# balance.net
KiCad netlist of a schematic drawn in EAGLE
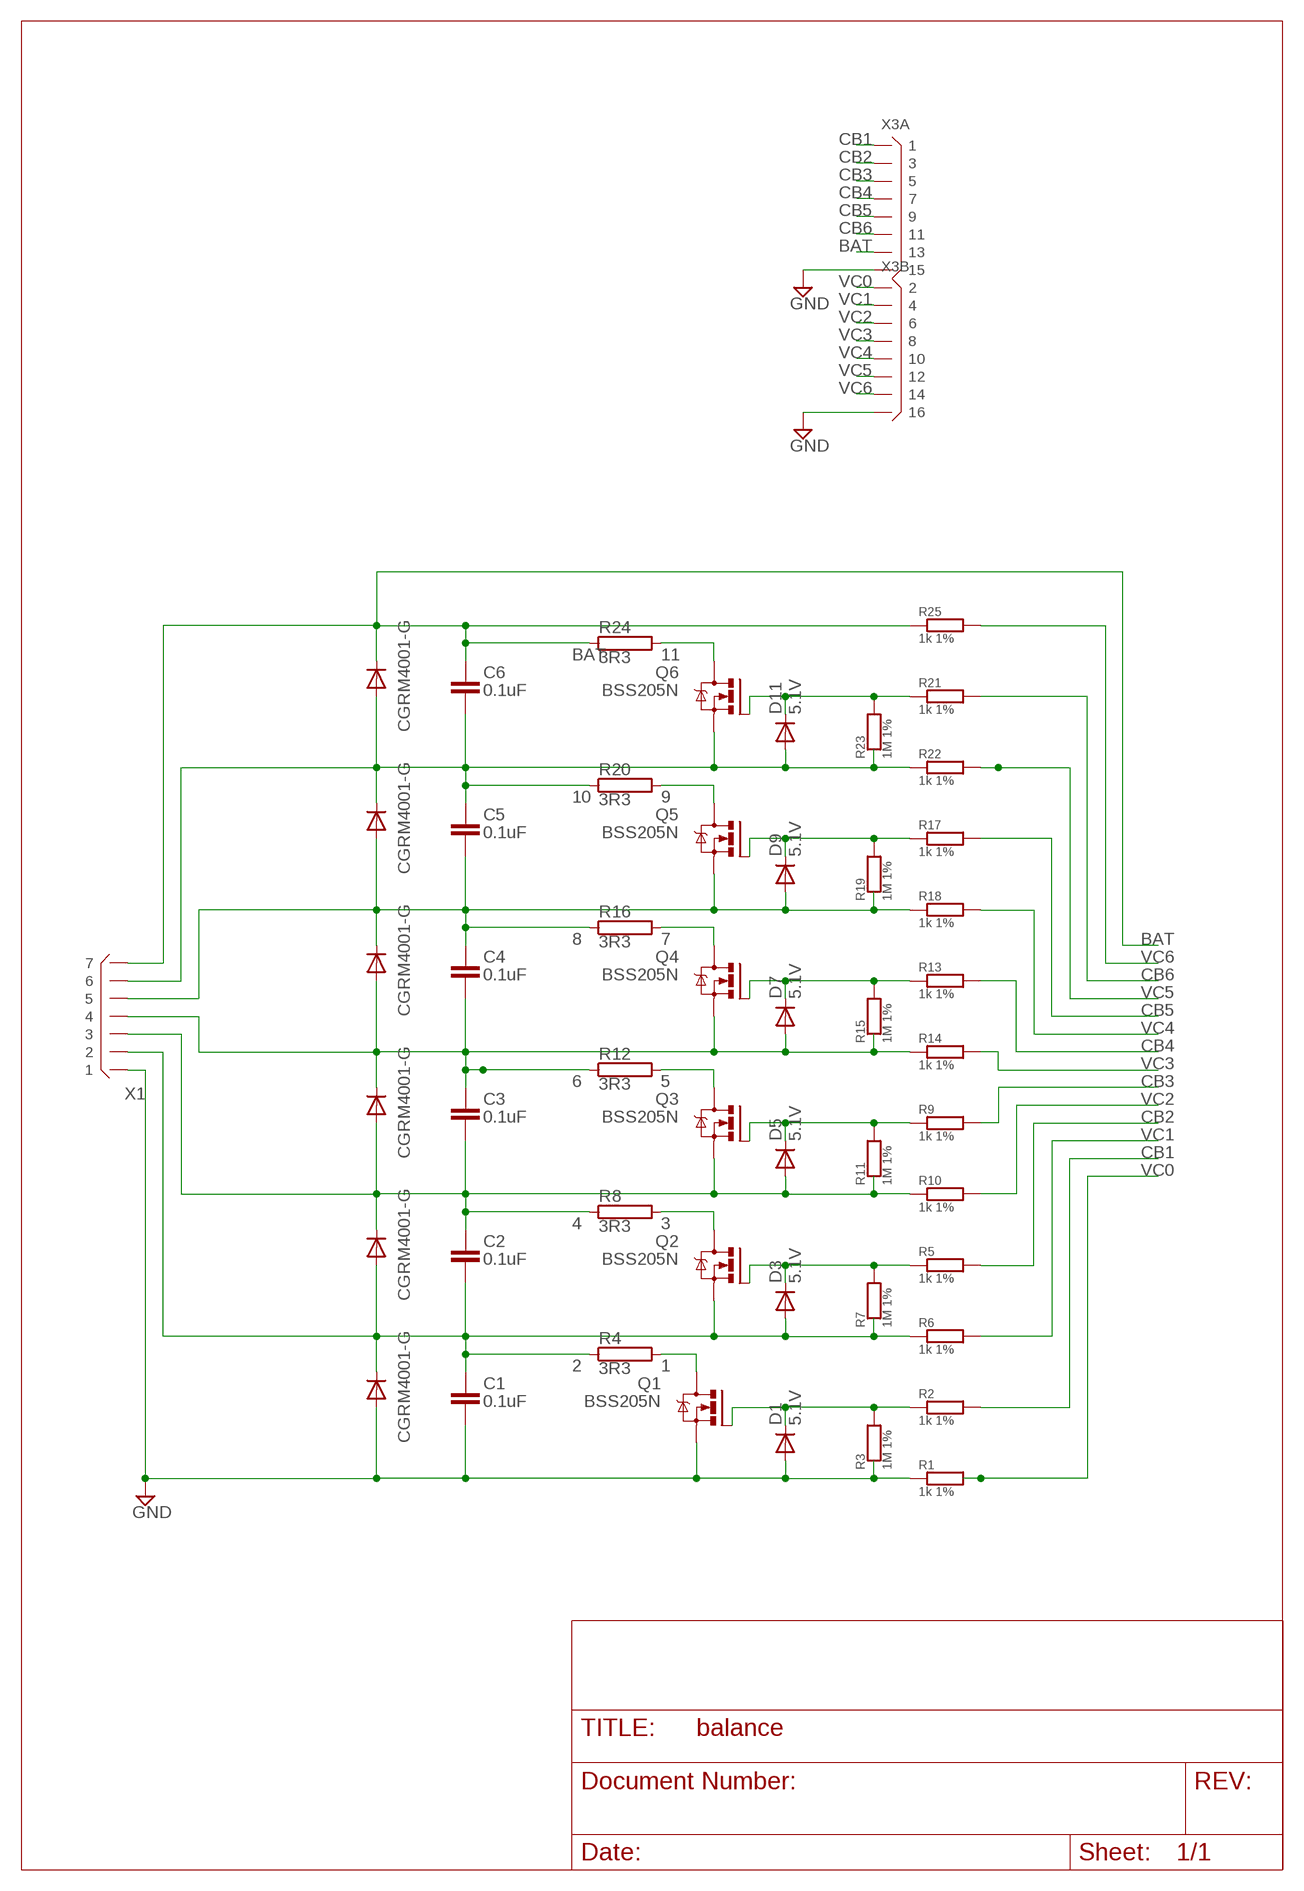
[diagram p0: schematic, sheet 1]

(export (version "E")
  (design (tool "Eeschema 10.0.6"))
  (components
    (comp (ref "C1")
      (value "0.1uF")
      (footprint "eagle-import:C0805")
      (libsource (lib "eagle-import") (part "CSTD"))
    )
    (comp (ref "C2")
      (value "0.1uF")
      (footprint "eagle-import:C0805")
      (libsource (lib "eagle-import") (part "CSTD"))
    )
    (comp (ref "C3")
      (value "0.1uF")
      (footprint "eagle-import:C0805")
      (libsource (lib "eagle-import") (part "CSTD"))
    )
    (comp (ref "C4")
      (value "0.1uF")
      (footprint "eagle-import:C0805")
      (libsource (lib "eagle-import") (part "CSTD"))
    )
    (comp (ref "C5")
      (value "0.1uF")
      (footprint "eagle-import:C0805")
      (libsource (lib "eagle-import") (part "CSTD"))
    )
    (comp (ref "C6")
      (value "0.1uF")
      (footprint "eagle-import:C0805")
      (libsource (lib "eagle-import") (part "CSTD"))
    )
    (comp (ref "D1")
      (value "5.1V")
      (footprint "eagle-import:SOD-323")
      (libsource (lib "eagle-import") (part "DIODESOD"))
    )
    (comp (ref "D2")
      (value "CGRM4001-G")
      (footprint "eagle-import:SOD-123_MINI-SMA")
      (libsource (lib "eagle-import") (part "CGRM400-G1"))
    )
    (comp (ref "D3")
      (value "5.1V")
      (footprint "eagle-import:SOD-323")
      (libsource (lib "eagle-import") (part "DIODESOD"))
    )
    (comp (ref "D4")
      (value "CGRM4001-G")
      (footprint "eagle-import:SOD-123_MINI-SMA")
      (libsource (lib "eagle-import") (part "CGRM400-G1"))
    )
    (comp (ref "D5")
      (value "5.1V")
      (footprint "eagle-import:SOD-323")
      (libsource (lib "eagle-import") (part "DIODESOD"))
    )
    (comp (ref "D6")
      (value "CGRM4001-G")
      (footprint "eagle-import:SOD-123_MINI-SMA")
      (libsource (lib "eagle-import") (part "CGRM400-G1"))
    )
    (comp (ref "D7")
      (value "5.1V")
      (footprint "eagle-import:SOD-323")
      (libsource (lib "eagle-import") (part "DIODESOD"))
    )
    (comp (ref "D8")
      (value "CGRM4001-G")
      (footprint "eagle-import:SOD-123_MINI-SMA")
      (libsource (lib "eagle-import") (part "CGRM400-G1"))
    )
    (comp (ref "D9")
      (value "5.1V")
      (footprint "eagle-import:SOD-323")
      (libsource (lib "eagle-import") (part "DIODESOD"))
    )
    (comp (ref "D10")
      (value "CGRM4001-G")
      (footprint "eagle-import:SOD-123_MINI-SMA")
      (libsource (lib "eagle-import") (part "CGRM400-G1"))
    )
    (comp (ref "D11")
      (value "5.1V")
      (footprint "eagle-import:SOD-323")
      (libsource (lib "eagle-import") (part "DIODESOD"))
    )
    (comp (ref "D12")
      (value "CGRM4001-G")
      (footprint "eagle-import:SOD-123_MINI-SMA")
      (libsource (lib "eagle-import") (part "CGRM400-G1"))
    )
    (comp (ref "Q1")
      (value "BSS205N")
      (footprint "eagle-import:SOT23")
      (libsource (lib "eagle-import") (part "BSS205N"))
    )
    (comp (ref "Q2")
      (value "BSS205N")
      (footprint "eagle-import:SOT23")
      (libsource (lib "eagle-import") (part "BSS205N"))
    )
    (comp (ref "Q3")
      (value "BSS205N")
      (footprint "eagle-import:SOT23")
      (libsource (lib "eagle-import") (part "BSS205N"))
    )
    (comp (ref "Q4")
      (value "BSS205N")
      (footprint "eagle-import:SOT23")
      (libsource (lib "eagle-import") (part "BSS205N"))
    )
    (comp (ref "Q5")
      (value "BSS205N")
      (footprint "eagle-import:SOT23")
      (libsource (lib "eagle-import") (part "BSS205N"))
    )
    (comp (ref "Q6")
      (value "BSS205N")
      (footprint "eagle-import:SOT23")
      (libsource (lib "eagle-import") (part "BSS205N"))
    )
    (comp (ref "R1")
      (value "1k 1%")
      (footprint "eagle-import:R0805")
      (libsource (lib "eagle-import") (part "useful_R"))
    )
    (comp (ref "R2")
      (value "1k 1%")
      (footprint "eagle-import:R0805")
      (libsource (lib "eagle-import") (part "useful_R"))
    )
    (comp (ref "R3")
      (value "1M 1%")
      (footprint "eagle-import:R0805")
      (libsource (lib "eagle-import") (part "useful_R"))
    )
    (comp (ref "R4")
      (value "3R3")
      (footprint "eagle-import:HS15")
      (libsource (lib "eagle-import") (part "R"))
    )
    (comp (ref "R5")
      (value "1k 1%")
      (footprint "eagle-import:R0805")
      (libsource (lib "eagle-import") (part "useful_R"))
    )
    (comp (ref "R6")
      (value "1k 1%")
      (footprint "eagle-import:R0805")
      (libsource (lib "eagle-import") (part "useful_R"))
    )
    (comp (ref "R7")
      (value "1M 1%")
      (footprint "eagle-import:R0805")
      (libsource (lib "eagle-import") (part "useful_R"))
    )
    (comp (ref "R8")
      (value "3R3")
      (footprint "eagle-import:HS15")
      (libsource (lib "eagle-import") (part "R"))
    )
    (comp (ref "R9")
      (value "1k 1%")
      (footprint "eagle-import:R0805")
      (libsource (lib "eagle-import") (part "useful_R"))
    )
    (comp (ref "R10")
      (value "1k 1%")
      (footprint "eagle-import:R0805")
      (libsource (lib "eagle-import") (part "useful_R"))
    )
    (comp (ref "R11")
      (value "1M 1%")
      (footprint "eagle-import:R0805")
      (libsource (lib "eagle-import") (part "useful_R"))
    )
    (comp (ref "R12")
      (value "3R3")
      (footprint "eagle-import:HS15")
      (libsource (lib "eagle-import") (part "R"))
    )
    (comp (ref "R13")
      (value "1k 1%")
      (footprint "eagle-import:R0805")
      (libsource (lib "eagle-import") (part "useful_R"))
    )
    (comp (ref "R14")
      (value "1k 1%")
      (footprint "eagle-import:R0805")
      (libsource (lib "eagle-import") (part "useful_R"))
    )
    (comp (ref "R15")
      (value "1M 1%")
      (footprint "eagle-import:R0805")
      (libsource (lib "eagle-import") (part "useful_R"))
    )
    (comp (ref "R16")
      (value "3R3")
      (footprint "eagle-import:HS15")
      (libsource (lib "eagle-import") (part "R"))
    )
    (comp (ref "R17")
      (value "1k 1%")
      (footprint "eagle-import:R0805")
      (libsource (lib "eagle-import") (part "useful_R"))
    )
    (comp (ref "R18")
      (value "1k 1%")
      (footprint "eagle-import:R0805")
      (libsource (lib "eagle-import") (part "useful_R"))
    )
    (comp (ref "R19")
      (value "1M 1%")
      (footprint "eagle-import:R0805")
      (libsource (lib "eagle-import") (part "useful_R"))
    )
    (comp (ref "R20")
      (value "3R3")
      (footprint "eagle-import:HS15")
      (libsource (lib "eagle-import") (part "R"))
    )
    (comp (ref "R21")
      (value "1k 1%")
      (footprint "eagle-import:R0805")
      (libsource (lib "eagle-import") (part "useful_R"))
    )
    (comp (ref "R22")
      (value "1k 1%")
      (footprint "eagle-import:R0805")
      (libsource (lib "eagle-import") (part "useful_R"))
    )
    (comp (ref "R23")
      (value "1M 1%")
      (footprint "eagle-import:R0805")
      (libsource (lib "eagle-import") (part "useful_R"))
    )
    (comp (ref "R24")
      (value "3R3")
      (footprint "eagle-import:HS15")
      (libsource (lib "eagle-import") (part "R"))
    )
    (comp (ref "R25")
      (value "1k 1%")
      (footprint "eagle-import:R0805")
      (libsource (lib "eagle-import") (part "useful_R"))
    )
    (comp (ref "X1")
      (value "B7B-XH")
      (footprint "eagle-import:B7B-XH")
      (libsource (lib "eagle-import") (part "?7B-XHB"))
    )
    (comp (ref "X3")
      (value "X08X2DR")
      (footprint "eagle-import:X16R-DIL")
      (libsource (lib "eagle-import") (part "X08X2DR"))
    )
  )
  (nets
    (net (code "1") (name "/1") (class "Default")
      (node (ref "Q1") (pin "3") (pinfunction "D_3") (pintype "passive"))
      (node (ref "R4") (pin "2") (pinfunction "2_2") (pintype "passive"))
    )
    (net (code "2") (name "/2") (class "Default")
      (node (ref "C1") (pin "2") (pinfunction "2_2") (pintype "passive"))
      (node (ref "C2") (pin "1") (pinfunction "1_1") (pintype "passive"))
      (node (ref "D2") (pin "C") (pinfunction "C_C") (pintype "passive"))
      (node (ref "D3") (pin "2") (pinfunction "A_2") (pintype "passive"))
      (node (ref "D4") (pin "A") (pinfunction "A_A") (pintype "passive"))
      (node (ref "Q2") (pin "2") (pinfunction "S_2") (pintype "passive"))
      (node (ref "R4") (pin "1") (pinfunction "1_1") (pintype "passive"))
      (node (ref "R6") (pin "1") (pinfunction "1_1") (pintype "passive"))
      (node (ref "R7") (pin "1") (pinfunction "1_1") (pintype "passive"))
      (node (ref "X1") (pin "P$2") (pinfunction "2_P$2") (pintype "bidirectional"))
    )
    (net (code "3") (name "/3") (class "Default")
      (node (ref "Q2") (pin "3") (pinfunction "D_3") (pintype "passive"))
      (node (ref "R8") (pin "2") (pinfunction "2_2") (pintype "passive"))
    )
    (net (code "4") (name "/4") (class "Default")
      (node (ref "C2") (pin "2") (pinfunction "2_2") (pintype "passive"))
      (node (ref "C3") (pin "1") (pinfunction "1_1") (pintype "passive"))
      (node (ref "D4") (pin "C") (pinfunction "C_C") (pintype "passive"))
      (node (ref "D5") (pin "2") (pinfunction "A_2") (pintype "passive"))
      (node (ref "D6") (pin "A") (pinfunction "A_A") (pintype "passive"))
      (node (ref "Q3") (pin "2") (pinfunction "S_2") (pintype "passive"))
      (node (ref "R10") (pin "1") (pinfunction "1_1") (pintype "passive"))
      (node (ref "R11") (pin "1") (pinfunction "1_1") (pintype "passive"))
      (node (ref "R8") (pin "1") (pinfunction "1_1") (pintype "passive"))
      (node (ref "X1") (pin "P$3") (pinfunction "3_P$3") (pintype "bidirectional"))
    )
    (net (code "5") (name "/5") (class "Default")
      (node (ref "Q3") (pin "3") (pinfunction "D_3") (pintype "passive"))
      (node (ref "R12") (pin "2") (pinfunction "2_2") (pintype "passive"))
    )
    (net (code "6") (name "/6") (class "Default")
      (node (ref "C3") (pin "2") (pinfunction "2_2") (pintype "passive"))
      (node (ref "C4") (pin "1") (pinfunction "1_1") (pintype "passive"))
      (node (ref "D6") (pin "C") (pinfunction "C_C") (pintype "passive"))
      (node (ref "D7") (pin "2") (pinfunction "A_2") (pintype "passive"))
      (node (ref "D8") (pin "A") (pinfunction "A_A") (pintype "passive"))
      (node (ref "Q4") (pin "2") (pinfunction "S_2") (pintype "passive"))
      (node (ref "R12") (pin "1") (pinfunction "1_1") (pintype "passive"))
      (node (ref "R14") (pin "1") (pinfunction "1_1") (pintype "passive"))
      (node (ref "R15") (pin "1") (pinfunction "1_1") (pintype "passive"))
      (node (ref "X1") (pin "P$4") (pinfunction "4_P$4") (pintype "bidirectional"))
    )
    (net (code "7") (name "/7") (class "Default")
      (node (ref "Q4") (pin "3") (pinfunction "D_3") (pintype "passive"))
      (node (ref "R16") (pin "2") (pinfunction "2_2") (pintype "passive"))
    )
    (net (code "8") (name "/8") (class "Default")
      (node (ref "C4") (pin "2") (pinfunction "2_2") (pintype "passive"))
      (node (ref "C5") (pin "1") (pinfunction "1_1") (pintype "passive"))
      (node (ref "D10") (pin "A") (pinfunction "A_A") (pintype "passive"))
      (node (ref "D8") (pin "C") (pinfunction "C_C") (pintype "passive"))
      (node (ref "D9") (pin "2") (pinfunction "A_2") (pintype "passive"))
      (node (ref "Q5") (pin "2") (pinfunction "S_2") (pintype "passive"))
      (node (ref "R16") (pin "1") (pinfunction "1_1") (pintype "passive"))
      (node (ref "R18") (pin "1") (pinfunction "1_1") (pintype "passive"))
      (node (ref "R19") (pin "1") (pinfunction "1_1") (pintype "passive"))
      (node (ref "X1") (pin "P$5") (pinfunction "5_P$5") (pintype "bidirectional"))
    )
    (net (code "9") (name "/9") (class "Default")
      (node (ref "Q5") (pin "3") (pinfunction "D_3") (pintype "passive"))
      (node (ref "R20") (pin "2") (pinfunction "2_2") (pintype "passive"))
    )
    (net (code "10") (name "/10") (class "Default")
      (node (ref "C5") (pin "2") (pinfunction "2_2") (pintype "passive"))
      (node (ref "C6") (pin "1") (pinfunction "1_1") (pintype "passive"))
      (node (ref "D10") (pin "C") (pinfunction "C_C") (pintype "passive"))
      (node (ref "D11") (pin "2") (pinfunction "A_2") (pintype "passive"))
      (node (ref "D12") (pin "A") (pinfunction "A_A") (pintype "passive"))
      (node (ref "Q6") (pin "2") (pinfunction "S_2") (pintype "passive"))
      (node (ref "R20") (pin "1") (pinfunction "1_1") (pintype "passive"))
      (node (ref "R22") (pin "1") (pinfunction "1_1") (pintype "passive"))
      (node (ref "R23") (pin "1") (pinfunction "1_1") (pintype "passive"))
      (node (ref "X1") (pin "P$6") (pinfunction "6_P$6") (pintype "bidirectional"))
    )
    (net (code "11") (name "/11") (class "Default")
      (node (ref "Q6") (pin "3") (pinfunction "D_3") (pintype "passive"))
      (node (ref "R24") (pin "2") (pinfunction "2_2") (pintype "passive"))
    )
    (net (code "12") (name "/BAT") (class "Default")
      (node (ref "C6") (pin "2") (pinfunction "2_2") (pintype "passive"))
      (node (ref "D12") (pin "C") (pinfunction "C_C") (pintype "passive"))
      (node (ref "R24") (pin "1") (pinfunction "1_1") (pintype "passive"))
      (node (ref "R25") (pin "1") (pinfunction "1_1") (pintype "passive"))
      (node (ref "X1") (pin "P$7") (pinfunction "7_P$7") (pintype "bidirectional"))
      (node (ref "X3") (pin "13") (pinfunction "13_13") (pintype "bidirectional"))
    )
    (net (code "13") (name "/CB1") (class "Default")
      (node (ref "R2") (pin "2") (pinfunction "2_2") (pintype "passive"))
      (node (ref "X3") (pin "1") (pinfunction "1_1") (pintype "bidirectional"))
    )
    (net (code "14") (name "/CB2") (class "Default")
      (node (ref "R5") (pin "2") (pinfunction "2_2") (pintype "passive"))
      (node (ref "X3") (pin "3") (pinfunction "3_3") (pintype "bidirectional"))
    )
    (net (code "15") (name "/CB3") (class "Default")
      (node (ref "R9") (pin "2") (pinfunction "2_2") (pintype "passive"))
      (node (ref "X3") (pin "5") (pinfunction "5_5") (pintype "bidirectional"))
    )
    (net (code "16") (name "/CB4") (class "Default")
      (node (ref "R13") (pin "2") (pinfunction "2_2") (pintype "passive"))
      (node (ref "X3") (pin "7") (pinfunction "7_7") (pintype "bidirectional"))
    )
    (net (code "17") (name "/CB5") (class "Default")
      (node (ref "R17") (pin "2") (pinfunction "2_2") (pintype "passive"))
      (node (ref "X3") (pin "9") (pinfunction "9_9") (pintype "bidirectional"))
    )
    (net (code "18") (name "/CB6") (class "Default")
      (node (ref "R21") (pin "2") (pinfunction "2_2") (pintype "passive"))
      (node (ref "X3") (pin "11") (pinfunction "11_11") (pintype "bidirectional"))
    )
    (net (code "19") (name "/VC0") (class "Default")
      (node (ref "R1") (pin "2") (pinfunction "2_2") (pintype "passive"))
      (node (ref "X3") (pin "2") (pinfunction "2_2") (pintype "bidirectional"))
    )
    (net (code "20") (name "/VC1") (class "Default")
      (node (ref "R6") (pin "2") (pinfunction "2_2") (pintype "passive"))
      (node (ref "X3") (pin "4") (pinfunction "4_4") (pintype "bidirectional"))
    )
    (net (code "21") (name "/VC2") (class "Default")
      (node (ref "R10") (pin "2") (pinfunction "2_2") (pintype "passive"))
      (node (ref "X3") (pin "6") (pinfunction "6_6") (pintype "bidirectional"))
    )
    (net (code "22") (name "/VC3") (class "Default")
      (node (ref "R14") (pin "2") (pinfunction "2_2") (pintype "passive"))
      (node (ref "X3") (pin "8") (pinfunction "8_8") (pintype "bidirectional"))
    )
    (net (code "23") (name "/VC4") (class "Default")
      (node (ref "R18") (pin "2") (pinfunction "2_2") (pintype "passive"))
      (node (ref "X3") (pin "10") (pinfunction "10_10") (pintype "bidirectional"))
    )
    (net (code "24") (name "/VC5") (class "Default")
      (node (ref "R22") (pin "2") (pinfunction "2_2") (pintype "passive"))
      (node (ref "X3") (pin "12") (pinfunction "12_12") (pintype "bidirectional"))
    )
    (net (code "25") (name "/VC6") (class "Default")
      (node (ref "R25") (pin "2") (pinfunction "2_2") (pintype "passive"))
      (node (ref "X3") (pin "14") (pinfunction "14_14") (pintype "bidirectional"))
    )
    (net (code "26") (name "GND") (class "Default")
      (node (ref "C1") (pin "1") (pinfunction "1_1") (pintype "passive"))
      (node (ref "D1") (pin "2") (pinfunction "A_2") (pintype "passive"))
      (node (ref "D2") (pin "A") (pinfunction "A_A") (pintype "passive"))
      (node (ref "Q1") (pin "2") (pinfunction "S_2") (pintype "passive"))
      (node (ref "R1") (pin "1") (pinfunction "1_1") (pintype "passive"))
      (node (ref "R3") (pin "1") (pinfunction "1_1") (pintype "passive"))
      (node (ref "X1") (pin "P$1") (pinfunction "1_P$1") (pintype "bidirectional"))
      (node (ref "X3") (pin "15") (pinfunction "15_15") (pintype "bidirectional"))
      (node (ref "X3") (pin "16") (pinfunction "16_16") (pintype "bidirectional"))
    )
    (net (code "27") (name "Net-(D1-C)") (class "Default")
      (node (ref "D1") (pin "1") (pinfunction "C_1") (pintype "passive"))
      (node (ref "Q1") (pin "1") (pinfunction "G_1") (pintype "passive"))
      (node (ref "R2") (pin "1") (pinfunction "1_1") (pintype "passive"))
      (node (ref "R3") (pin "2") (pinfunction "2_2") (pintype "passive"))
    )
    (net (code "28") (name "Net-(D3-C)") (class "Default")
      (node (ref "D3") (pin "1") (pinfunction "C_1") (pintype "passive"))
      (node (ref "Q2") (pin "1") (pinfunction "G_1") (pintype "passive"))
      (node (ref "R5") (pin "1") (pinfunction "1_1") (pintype "passive"))
      (node (ref "R7") (pin "2") (pinfunction "2_2") (pintype "passive"))
    )
    (net (code "29") (name "Net-(D5-C)") (class "Default")
      (node (ref "D5") (pin "1") (pinfunction "C_1") (pintype "passive"))
      (node (ref "Q3") (pin "1") (pinfunction "G_1") (pintype "passive"))
      (node (ref "R11") (pin "2") (pinfunction "2_2") (pintype "passive"))
      (node (ref "R9") (pin "1") (pinfunction "1_1") (pintype "passive"))
    )
    (net (code "30") (name "Net-(D7-C)") (class "Default")
      (node (ref "D7") (pin "1") (pinfunction "C_1") (pintype "passive"))
      (node (ref "Q4") (pin "1") (pinfunction "G_1") (pintype "passive"))
      (node (ref "R13") (pin "1") (pinfunction "1_1") (pintype "passive"))
      (node (ref "R15") (pin "2") (pinfunction "2_2") (pintype "passive"))
    )
    (net (code "31") (name "Net-(D9-C)") (class "Default")
      (node (ref "D9") (pin "1") (pinfunction "C_1") (pintype "passive"))
      (node (ref "Q5") (pin "1") (pinfunction "G_1") (pintype "passive"))
      (node (ref "R17") (pin "1") (pinfunction "1_1") (pintype "passive"))
      (node (ref "R19") (pin "2") (pinfunction "2_2") (pintype "passive"))
    )
    (net (code "32") (name "Net-(D11-C)") (class "Default")
      (node (ref "D11") (pin "1") (pinfunction "C_1") (pintype "passive"))
      (node (ref "Q6") (pin "1") (pinfunction "G_1") (pintype "passive"))
      (node (ref "R21") (pin "1") (pinfunction "1_1") (pintype "passive"))
      (node (ref "R23") (pin "2") (pinfunction "2_2") (pintype "passive"))
    )
  )
)
